# AdcPmodClock.net
KiCad netlist of a schematic drawn in Altium Designer
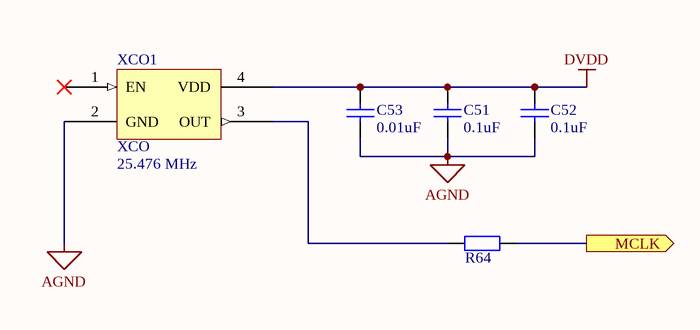
[diagram p0: AdcPmodClock.SchDoc]

(export (version "E")
  (design (tool "Eeschema 10.0.6"))
  (components
    (comp (ref "C51")
      (value "0.1uF")
      (footprint "CAP0805")
      (description "Ceramic X7R")
      (fields (field (name "MANUFACTURER") "AVX") (field (name "MFR. PART NO.") "08055C104KAT2A"))
      (libsource (lib "AdcPmod") (part "CAP"))
    )
    (comp (ref "C52")
      (value "0.1uF")
      (footprint "CAP0805")
      (description "Ceramic X7R")
      (fields (field (name "MANUFACTURER") "AVX") (field (name "MFR. PART NO.") "08055C104KAT2A"))
      (libsource (lib "AdcPmod") (part "CAP"))
    )
    (comp (ref "C53")
      (value "0.01uF")
      (footprint "CAP0805")
      (description "Ceramic X7R")
      (fields
        (field (name "MANUFACTURER") "Murata Electronics")
        (field (name "MFR. PART NO.") "GRM216R71E103KA01D")
      )
      (libsource (lib "AdcPmod") (part "CAP"))
    )
    (comp (ref "R64")
      (value "RES")
      (footprint "RES0805")
      (description "Resistor")
      (libsource (lib "AdcPmod") (part "RES"))
    )
    (comp (ref "XCO1")
      (value "XCO")
      (footprint "XCO 5x3.2mm (HS)")
      (description "Standard Clock Oscillator")
      (fields
        (field (name "FREQUENCY") "25.476 MHz")
        (field (name "MANUFACTURER") "ABRACON")
        (field (name "MFR. PART NO.") "ASFL1-24.576MHZ-EC-T")
      )
      (libsource (lib "AdcPmod") (part "XCO"))
    )
  )
  (nets
    (net (code "1") (name "/MCLK") (class "Default")
      (node (ref "R64") (pin "2") (pinfunction "2_2") (pintype "passive"))
    )
    (net (code "2") (name "AGND") (class "Default")
      (node (ref "C51") (pin "1") (pinfunction "1_1") (pintype "passive"))
      (node (ref "C52") (pin "1") (pinfunction "1_1") (pintype "passive"))
      (node (ref "C53") (pin "2") (pinfunction "2_2") (pintype "passive"))
      (node (ref "XCO1") (pin "2") (pinfunction "GND_2") (pintype "power_in"))
    )
    (net (code "3") (name "DVDD") (class "Default")
      (node (ref "C51") (pin "2") (pinfunction "2_2") (pintype "passive"))
      (node (ref "C52") (pin "2") (pinfunction "2_2") (pintype "passive"))
      (node (ref "C53") (pin "1") (pinfunction "1_1") (pintype "passive"))
      (node (ref "XCO1") (pin "4") (pinfunction "VDD_4") (pintype "power_in"))
    )
    (net (code "4") (name "Net-(XCO1-OUT)") (class "Default")
      (node (ref "R64") (pin "1") (pinfunction "1_1") (pintype "passive"))
      (node (ref "XCO1") (pin "3") (pinfunction "OUT_3") (pintype "output"))
    )
    (net (code "5") (name "unconnected-(XCO1-EN-Pad1)") (class "Default")
      (node (ref "XCO1") (pin "1") (pinfunction "EN_1") (pintype "input+no_connect"))
    )
  )
)
